# 17-ECP5_FPGA_2.net
KiCad netlist of a schematic drawn in Altium Designer
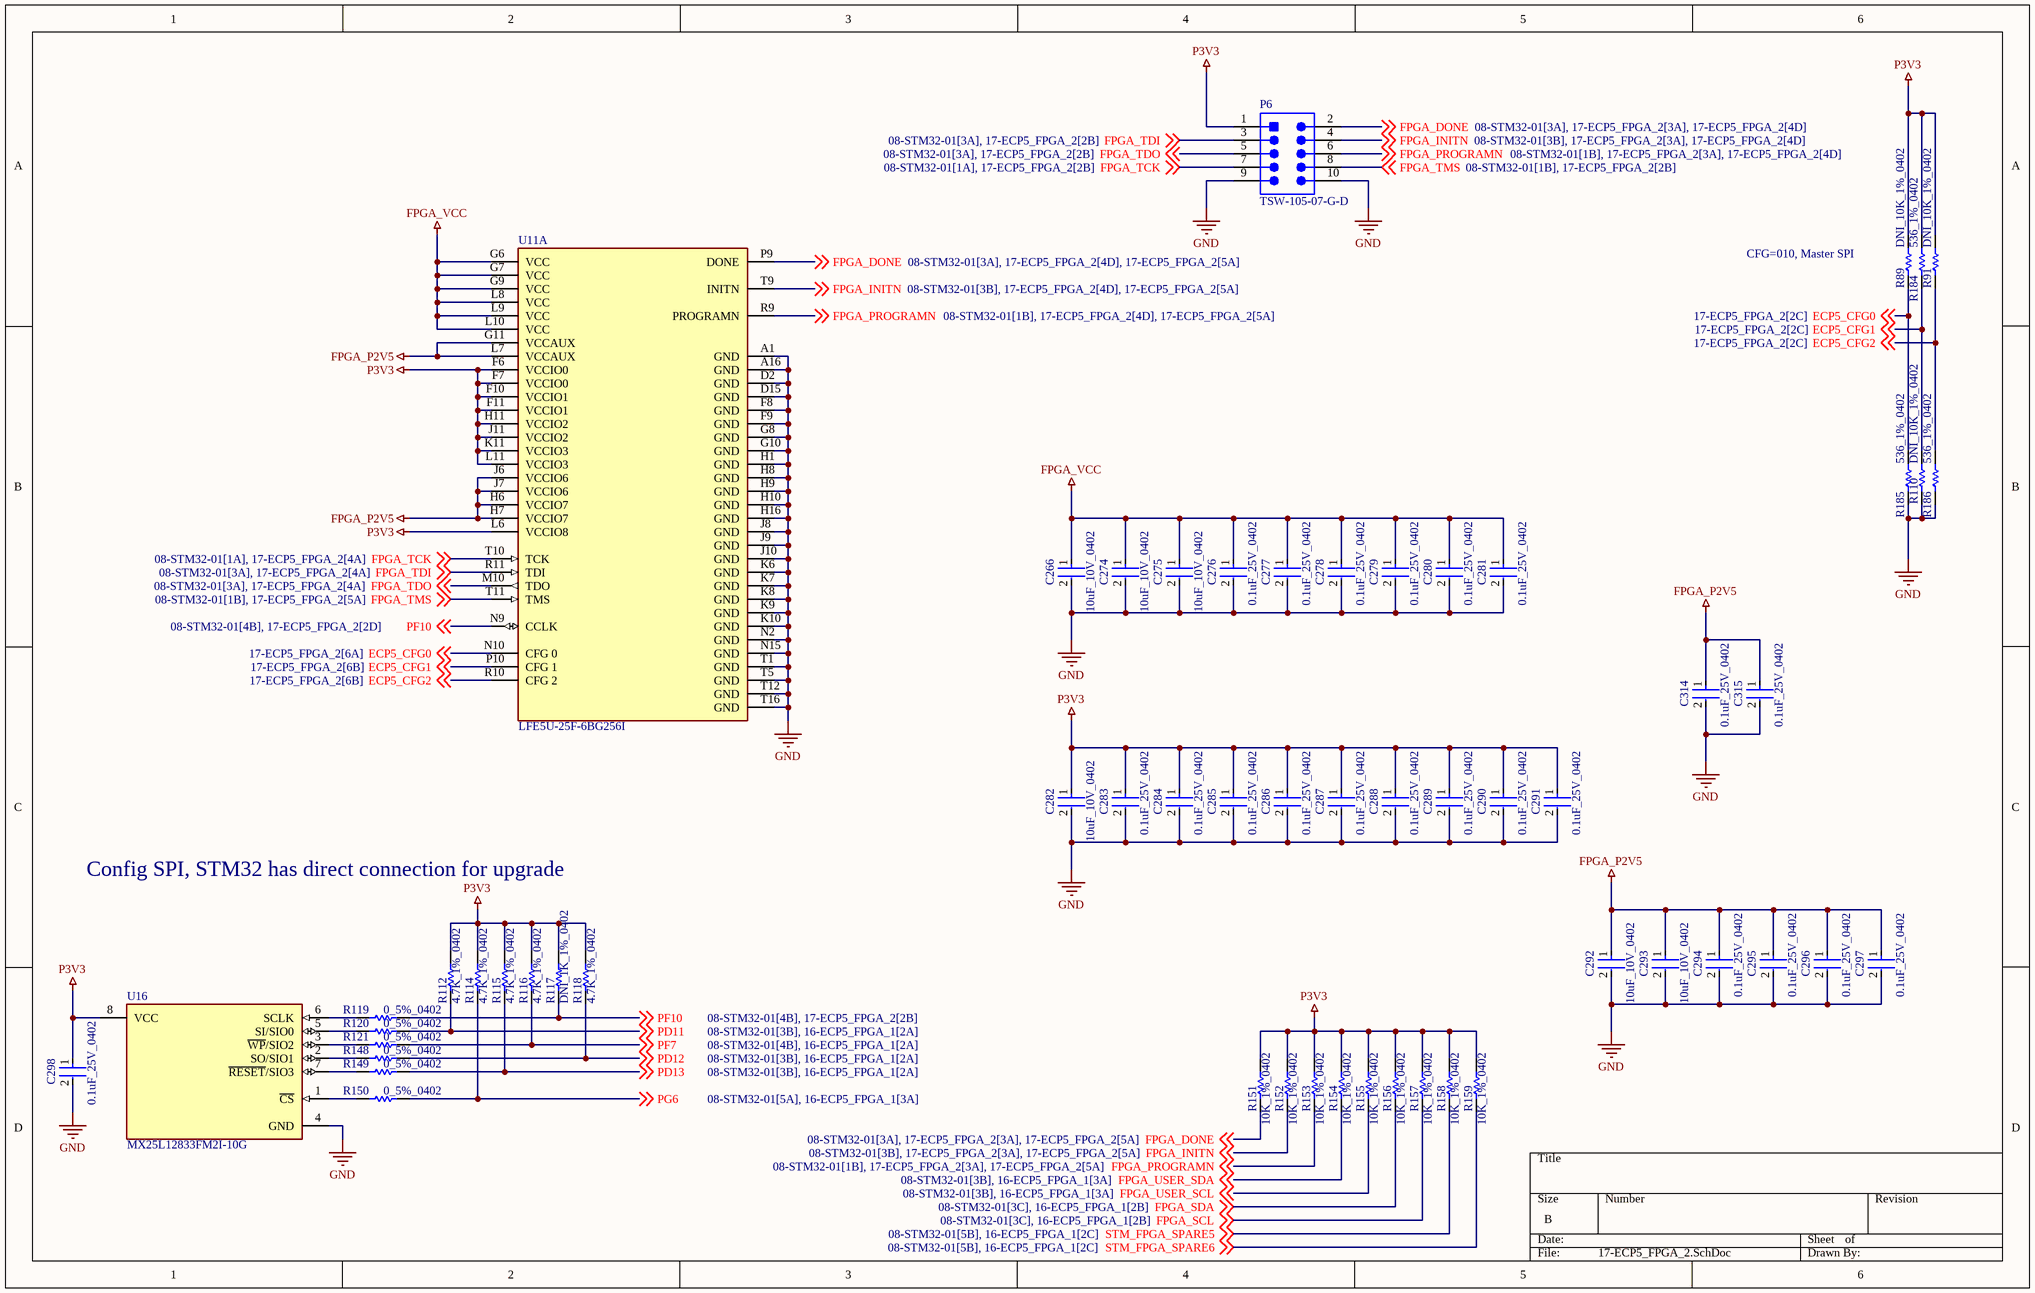
[diagram p0: 17-ECP5_FPGA_2.SchDoc]

(export (version "E")
  (design (tool "Eeschema 10.0.6"))
  (components
    (comp (ref "C266")
      (value "10uF_10V_0402")
      (footprint "FP-CL05A106MP5NUNC-MFG")
      (description "CAP CER 10UF 10V X5R 0402")
      (fields
        (field (name "OCTOPART") "https://octopart.com/cl05a106mp5nunc-samsung-22457395")
        (field (name "TOLERANCE") "20%")
      )
      (libsource (lib "Altium Content Vault") (part "b4654b650e69147ec39a6b967a45e02"))
    )
    (comp (ref "C274")
      (value "10uF_10V_0402")
      (footprint "FP-CL05A106MP5NUNC-MFG")
      (description "CAP CER 10UF 10V X5R 0402")
      (fields
        (field (name "OCTOPART") "https://octopart.com/cl05a106mp5nunc-samsung-22457395")
        (field (name "TOLERANCE") "20%")
      )
      (libsource (lib "Altium Content Vault") (part "b4654b650e69147ec39a6b967a45e02"))
    )
    (comp (ref "C275")
      (value "10uF_10V_0402")
      (footprint "FP-CL05A106MP5NUNC-MFG")
      (description "CAP CER 10UF 10V X5R 0402")
      (fields
        (field (name "OCTOPART") "https://octopart.com/cl05a106mp5nunc-samsung-22457395")
        (field (name "TOLERANCE") "20%")
      )
      (libsource (lib "Altium Content Vault") (part "b4654b650e69147ec39a6b967a45e02"))
    )
    (comp (ref "C276")
      (value "0.1uF_25V_0402")
      (footprint "FP-0402-L_1_0_1-W_0_5_0_1-IPC_C")
      (description "General Purpose Ceramic Capacitor, 0402, 100nF, 10%, X7R, 15%, 25V")
      (fields (field (name "VOLTAGE") "25V") (field (name "TOLERANCE") "10%"))
      (libsource (lib "Altium Content Vault") (part "b4654b650e69147ec39a6b967a45e02"))
    )
    (comp (ref "C277")
      (value "0.1uF_25V_0402")
      (footprint "FP-0402-L_1_0_1-W_0_5_0_1-IPC_C")
      (description "General Purpose Ceramic Capacitor, 0402, 100nF, 10%, X7R, 15%, 25V")
      (fields (field (name "VOLTAGE") "25V") (field (name "TOLERANCE") "10%"))
      (libsource (lib "Altium Content Vault") (part "b4654b650e69147ec39a6b967a45e02"))
    )
    (comp (ref "C278")
      (value "0.1uF_25V_0402")
      (footprint "FP-0402-L_1_0_1-W_0_5_0_1-IPC_C")
      (description "General Purpose Ceramic Capacitor, 0402, 100nF, 10%, X7R, 15%, 25V")
      (fields (field (name "VOLTAGE") "25V") (field (name "TOLERANCE") "10%"))
      (libsource (lib "Altium Content Vault") (part "b4654b650e69147ec39a6b967a45e02"))
    )
    (comp (ref "C279")
      (value "0.1uF_25V_0402")
      (footprint "FP-0402-L_1_0_1-W_0_5_0_1-IPC_C")
      (description "General Purpose Ceramic Capacitor, 0402, 100nF, 10%, X7R, 15%, 25V")
      (fields (field (name "VOLTAGE") "25V") (field (name "TOLERANCE") "10%"))
      (libsource (lib "Altium Content Vault") (part "b4654b650e69147ec39a6b967a45e02"))
    )
    (comp (ref "C280")
      (value "0.1uF_25V_0402")
      (footprint "FP-0402-L_1_0_1-W_0_5_0_1-IPC_C")
      (description "General Purpose Ceramic Capacitor, 0402, 100nF, 10%, X7R, 15%, 25V")
      (fields (field (name "VOLTAGE") "25V") (field (name "TOLERANCE") "10%"))
      (libsource (lib "Altium Content Vault") (part "b4654b650e69147ec39a6b967a45e02"))
    )
    (comp (ref "C281")
      (value "0.1uF_25V_0402")
      (footprint "FP-0402-L_1_0_1-W_0_5_0_1-IPC_C")
      (description "General Purpose Ceramic Capacitor, 0402, 100nF, 10%, X7R, 15%, 25V")
      (fields (field (name "VOLTAGE") "25V") (field (name "TOLERANCE") "10%"))
      (libsource (lib "Altium Content Vault") (part "b4654b650e69147ec39a6b967a45e02"))
    )
    (comp (ref "C282")
      (value "10uF_10V_0402")
      (footprint "FP-CL05A106MP5NUNC-MFG")
      (description "CAP CER 10UF 10V X5R 0402")
      (fields
        (field (name "OCTOPART") "https://octopart.com/cl05a106mp5nunc-samsung-22457395")
        (field (name "TOLERANCE") "20%")
      )
      (libsource (lib "Altium Content Vault") (part "b4654b650e69147ec39a6b967a45e02"))
    )
    (comp (ref "C283")
      (value "0.1uF_25V_0402")
      (footprint "FP-0402-L_1_0_1-W_0_5_0_1-IPC_C")
      (description "General Purpose Ceramic Capacitor, 0402, 100nF, 10%, X7R, 15%, 25V")
      (fields (field (name "VOLTAGE") "25V") (field (name "TOLERANCE") "10%"))
      (libsource (lib "Altium Content Vault") (part "b4654b650e69147ec39a6b967a45e02"))
    )
    (comp (ref "C284")
      (value "0.1uF_25V_0402")
      (footprint "FP-0402-L_1_0_1-W_0_5_0_1-IPC_C")
      (description "General Purpose Ceramic Capacitor, 0402, 100nF, 10%, X7R, 15%, 25V")
      (fields (field (name "VOLTAGE") "25V") (field (name "TOLERANCE") "10%"))
      (libsource (lib "Altium Content Vault") (part "b4654b650e69147ec39a6b967a45e02"))
    )
    (comp (ref "C285")
      (value "0.1uF_25V_0402")
      (footprint "FP-0402-L_1_0_1-W_0_5_0_1-IPC_C")
      (description "General Purpose Ceramic Capacitor, 0402, 100nF, 10%, X7R, 15%, 25V")
      (fields (field (name "VOLTAGE") "25V") (field (name "TOLERANCE") "10%"))
      (libsource (lib "Altium Content Vault") (part "b4654b650e69147ec39a6b967a45e02"))
    )
    (comp (ref "C286")
      (value "0.1uF_25V_0402")
      (footprint "FP-0402-L_1_0_1-W_0_5_0_1-IPC_C")
      (description "General Purpose Ceramic Capacitor, 0402, 100nF, 10%, X7R, 15%, 25V")
      (fields (field (name "VOLTAGE") "25V") (field (name "TOLERANCE") "10%"))
      (libsource (lib "Altium Content Vault") (part "b4654b650e69147ec39a6b967a45e02"))
    )
    (comp (ref "C287")
      (value "0.1uF_25V_0402")
      (footprint "FP-0402-L_1_0_1-W_0_5_0_1-IPC_C")
      (description "General Purpose Ceramic Capacitor, 0402, 100nF, 10%, X7R, 15%, 25V")
      (fields (field (name "VOLTAGE") "25V") (field (name "TOLERANCE") "10%"))
      (libsource (lib "Altium Content Vault") (part "b4654b650e69147ec39a6b967a45e02"))
    )
    (comp (ref "C288")
      (value "0.1uF_25V_0402")
      (footprint "FP-0402-L_1_0_1-W_0_5_0_1-IPC_C")
      (description "General Purpose Ceramic Capacitor, 0402, 100nF, 10%, X7R, 15%, 25V")
      (fields (field (name "VOLTAGE") "25V") (field (name "TOLERANCE") "10%"))
      (libsource (lib "Altium Content Vault") (part "b4654b650e69147ec39a6b967a45e02"))
    )
    (comp (ref "C289")
      (value "0.1uF_25V_0402")
      (footprint "FP-0402-L_1_0_1-W_0_5_0_1-IPC_C")
      (description "General Purpose Ceramic Capacitor, 0402, 100nF, 10%, X7R, 15%, 25V")
      (fields (field (name "VOLTAGE") "25V") (field (name "TOLERANCE") "10%"))
      (libsource (lib "Altium Content Vault") (part "b4654b650e69147ec39a6b967a45e02"))
    )
    (comp (ref "C290")
      (value "0.1uF_25V_0402")
      (footprint "FP-0402-L_1_0_1-W_0_5_0_1-IPC_C")
      (description "General Purpose Ceramic Capacitor, 0402, 100nF, 10%, X7R, 15%, 25V")
      (fields (field (name "VOLTAGE") "25V") (field (name "TOLERANCE") "10%"))
      (libsource (lib "Altium Content Vault") (part "b4654b650e69147ec39a6b967a45e02"))
    )
    (comp (ref "C291")
      (value "0.1uF_25V_0402")
      (footprint "FP-0402-L_1_0_1-W_0_5_0_1-IPC_C")
      (description "General Purpose Ceramic Capacitor, 0402, 100nF, 10%, X7R, 15%, 25V")
      (fields (field (name "VOLTAGE") "25V") (field (name "TOLERANCE") "10%"))
      (libsource (lib "Altium Content Vault") (part "b4654b650e69147ec39a6b967a45e02"))
    )
    (comp (ref "C292")
      (value "10uF_10V_0402")
      (footprint "FP-CL05A106MP5NUNC-MFG")
      (description "CAP CER 10UF 10V X5R 0402")
      (fields
        (field (name "OCTOPART") "https://octopart.com/cl05a106mp5nunc-samsung-22457395")
        (field (name "TOLERANCE") "20%")
      )
      (libsource (lib "Altium Content Vault") (part "b4654b650e69147ec39a6b967a45e02"))
    )
    (comp (ref "C293")
      (value "10uF_10V_0402")
      (footprint "FP-CL05A106MP5NUNC-MFG")
      (description "CAP CER 10UF 10V X5R 0402")
      (fields
        (field (name "OCTOPART") "https://octopart.com/cl05a106mp5nunc-samsung-22457395")
        (field (name "TOLERANCE") "20%")
      )
      (libsource (lib "Altium Content Vault") (part "b4654b650e69147ec39a6b967a45e02"))
    )
    (comp (ref "C294")
      (value "0.1uF_25V_0402")
      (footprint "FP-0402-L_1_0_1-W_0_5_0_1-IPC_C")
      (description "General Purpose Ceramic Capacitor, 0402, 100nF, 10%, X7R, 15%, 25V")
      (fields (field (name "VOLTAGE") "25V") (field (name "TOLERANCE") "10%"))
      (libsource (lib "Altium Content Vault") (part "b4654b650e69147ec39a6b967a45e02"))
    )
    (comp (ref "C295")
      (value "0.1uF_25V_0402")
      (footprint "FP-0402-L_1_0_1-W_0_5_0_1-IPC_C")
      (description "General Purpose Ceramic Capacitor, 0402, 100nF, 10%, X7R, 15%, 25V")
      (fields (field (name "VOLTAGE") "25V") (field (name "TOLERANCE") "10%"))
      (libsource (lib "Altium Content Vault") (part "b4654b650e69147ec39a6b967a45e02"))
    )
    (comp (ref "C296")
      (value "0.1uF_25V_0402")
      (footprint "FP-0402-L_1_0_1-W_0_5_0_1-IPC_C")
      (description "General Purpose Ceramic Capacitor, 0402, 100nF, 10%, X7R, 15%, 25V")
      (fields (field (name "VOLTAGE") "25V") (field (name "TOLERANCE") "10%"))
      (libsource (lib "Altium Content Vault") (part "b4654b650e69147ec39a6b967a45e02"))
    )
    (comp (ref "C297")
      (value "0.1uF_25V_0402")
      (footprint "FP-0402-L_1_0_1-W_0_5_0_1-IPC_C")
      (description "General Purpose Ceramic Capacitor, 0402, 100nF, 10%, X7R, 15%, 25V")
      (fields (field (name "VOLTAGE") "25V") (field (name "TOLERANCE") "10%"))
      (libsource (lib "Altium Content Vault") (part "b4654b650e69147ec39a6b967a45e02"))
    )
    (comp (ref "C298")
      (value "0.1uF_25V_0402")
      (footprint "FP-0402-L_1_0_1-W_0_5_0_1-IPC_C")
      (description "General Purpose Ceramic Capacitor, 0402, 100nF, 10%, X7R, 15%, 25V")
      (fields (field (name "VOLTAGE") "25V") (field (name "TOLERANCE") "10%"))
      (libsource (lib "Altium Content Vault") (part "b4654b650e69147ec39a6b967a45e02"))
    )
    (comp (ref "C314")
      (value "0.1uF_25V_0402")
      (footprint "FP-0402-L_1_0_1-W_0_5_0_1-IPC_C")
      (description "General Purpose Ceramic Capacitor, 0402, 100nF, 10%, X7R, 15%, 25V")
      (fields (field (name "VOLTAGE") "25V") (field (name "TOLERANCE") "10%"))
      (libsource (lib "Altium Content Vault") (part "b4654b650e69147ec39a6b967a45e02"))
    )
    (comp (ref "C315")
      (value "0.1uF_25V_0402")
      (footprint "FP-0402-L_1_0_1-W_0_5_0_1-IPC_C")
      (description "General Purpose Ceramic Capacitor, 0402, 100nF, 10%, X7R, 15%, 25V")
      (fields (field (name "VOLTAGE") "25V") (field (name "TOLERANCE") "10%"))
      (libsource (lib "Altium Content Vault") (part "b4654b650e69147ec39a6b967a45e02"))
    )
    (comp (ref "P6")
      (value "TSW-105-07-G-D")
      (footprint "SMTC-TSW-105-07-G-D_V")
      (fields (field (name "MANUFACTURER") "Samtec-Inc."))
      (libsource (lib "Altium Content Vault") (part "CN-2P-M-R10"))
    )
    (comp (ref "R89")
      (value "DNI_10K_1%_0402")
      (footprint "RESC1005X40X25NL10T10")
      (fields (field (name "MANUFACTURER") "Bourns") (field (name "PART NUMBER") "CR0402-FX-1002GLF"))
      (libsource (lib "Altium Content Vault") (part "RES"))
    )
    (comp (ref "R91")
      (value "DNI_10K_1%_0402")
      (footprint "RESC1005X40X25NL10T10")
      (fields (field (name "MANUFACTURER") "Bourns") (field (name "PART NUMBER") "CR0402-FX-1002GLF"))
      (libsource (lib "Altium Content Vault") (part "RES"))
    )
    (comp (ref "R110")
      (value "DNI_10K_1%_0402")
      (footprint "RESC1005X40X25NL10T10")
      (fields (field (name "MANUFACTURER") "Bourns") (field (name "PART NUMBER") "CR0402-FX-1002GLF"))
      (libsource (lib "Altium Content Vault") (part "RES"))
    )
    (comp (ref "R112")
      (value "4.7K_1%_0402")
      (footprint "RESC1005X40X25NL10T10")
      (fields (field (name "MANUFACTURER") "Bourns") (field (name "PART NUMBER") "CR0402-FX-4701GLF"))
      (libsource (lib "Altium Content Vault") (part "RES"))
    )
    (comp (ref "R114")
      (value "4.7K_1%_0402")
      (footprint "RESC1005X40X25NL10T10")
      (fields (field (name "MANUFACTURER") "Bourns") (field (name "PART NUMBER") "CR0402-FX-4701GLF"))
      (libsource (lib "Altium Content Vault") (part "RES"))
    )
    (comp (ref "R115")
      (value "4.7K_1%_0402")
      (footprint "RESC1005X40X25NL10T10")
      (fields (field (name "MANUFACTURER") "Bourns") (field (name "PART NUMBER") "CR0402-FX-4701GLF"))
      (libsource (lib "Altium Content Vault") (part "RES"))
    )
    (comp (ref "R116")
      (value "4.7K_1%_0402")
      (footprint "RESC1005X40X25NL10T10")
      (fields (field (name "MANUFACTURER") "Bourns") (field (name "PART NUMBER") "CR0402-FX-4701GLF"))
      (libsource (lib "Altium Content Vault") (part "RES"))
    )
    (comp (ref "R117")
      (value "DNI_1K_1%_0402")
      (footprint "RESC1005X40X25LL05T10")
      (fields (field (name "PART NUMBER") "CRCW04021K00FKEDHP") (field (name "MANUFACTURER") "Vishay Dale"))
      (libsource (lib "Altium Content Vault") (part "RES"))
    )
    (comp (ref "R118")
      (value "4.7K_1%_0402")
      (footprint "RESC1005X40X25NL10T10")
      (fields (field (name "MANUFACTURER") "Bourns") (field (name "PART NUMBER") "CR0402-FX-4701GLF"))
      (libsource (lib "Altium Content Vault") (part "RES"))
    )
    (comp (ref "R119")
      (value "0_5%_0402")
      (footprint "RESC1005X40X25NL05T10")
      (fields (field (name "MANUFACTURER") "Panasonic") (field (name "PART NUMBER") "ERJ-U020R00X"))
      (libsource (lib "Altium Content Vault") (part "RES"))
    )
    (comp (ref "R120")
      (value "0_5%_0402")
      (footprint "RESC1005X40X25NL05T10")
      (fields (field (name "MANUFACTURER") "Panasonic") (field (name "PART NUMBER") "ERJ-U020R00X"))
      (libsource (lib "Altium Content Vault") (part "RES"))
    )
    (comp (ref "R121")
      (value "0_5%_0402")
      (footprint "RESC1005X40X25NL05T10")
      (fields (field (name "MANUFACTURER") "Panasonic") (field (name "PART NUMBER") "ERJ-U020R00X"))
      (libsource (lib "Altium Content Vault") (part "RES"))
    )
    (comp (ref "R148")
      (value "0_5%_0402")
      (footprint "RESC1005X40X25NL05T10")
      (fields (field (name "MANUFACTURER") "Panasonic") (field (name "PART NUMBER") "ERJ-U020R00X"))
      (libsource (lib "Altium Content Vault") (part "RES"))
    )
    (comp (ref "R149")
      (value "0_5%_0402")
      (footprint "RESC1005X40X25NL05T10")
      (fields (field (name "MANUFACTURER") "Panasonic") (field (name "PART NUMBER") "ERJ-U020R00X"))
      (libsource (lib "Altium Content Vault") (part "RES"))
    )
    (comp (ref "R150")
      (value "0_5%_0402")
      (footprint "RESC1005X40X25NL05T10")
      (fields (field (name "MANUFACTURER") "Panasonic") (field (name "PART NUMBER") "ERJ-U020R00X"))
      (libsource (lib "Altium Content Vault") (part "RES"))
    )
    (comp (ref "R151")
      (value "10K_1%_0402")
      (footprint "RESC1005X40X25NL10T10")
      (fields (field (name "MANUFACTURER") "Bourns") (field (name "PART NUMBER") "CR0402-FX-1002GLF"))
      (libsource (lib "Altium Content Vault") (part "RES"))
    )
    (comp (ref "R152")
      (value "10K_1%_0402")
      (footprint "RESC1005X40X25NL10T10")
      (fields (field (name "MANUFACTURER") "Bourns") (field (name "PART NUMBER") "CR0402-FX-1002GLF"))
      (libsource (lib "Altium Content Vault") (part "RES"))
    )
    (comp (ref "R153")
      (value "10K_1%_0402")
      (footprint "RESC1005X40X25NL10T10")
      (fields (field (name "MANUFACTURER") "Bourns") (field (name "PART NUMBER") "CR0402-FX-1002GLF"))
      (libsource (lib "Altium Content Vault") (part "RES"))
    )
    (comp (ref "R154")
      (value "10K_1%_0402")
      (footprint "RESC1005X40X25NL10T10")
      (fields (field (name "MANUFACTURER") "Bourns") (field (name "PART NUMBER") "CR0402-FX-1002GLF"))
      (libsource (lib "Altium Content Vault") (part "RES"))
    )
    (comp (ref "R155")
      (value "10K_1%_0402")
      (footprint "RESC1005X40X25NL10T10")
      (fields (field (name "MANUFACTURER") "Bourns") (field (name "PART NUMBER") "CR0402-FX-1002GLF"))
      (libsource (lib "Altium Content Vault") (part "RES"))
    )
    (comp (ref "R156")
      (value "10K_1%_0402")
      (footprint "RESC1005X40X25NL10T10")
      (fields (field (name "MANUFACTURER") "Bourns") (field (name "PART NUMBER") "CR0402-FX-1002GLF"))
      (libsource (lib "Altium Content Vault") (part "RES"))
    )
    (comp (ref "R157")
      (value "10K_1%_0402")
      (footprint "RESC1005X40X25NL10T10")
      (fields (field (name "MANUFACTURER") "Bourns") (field (name "PART NUMBER") "CR0402-FX-1002GLF"))
      (libsource (lib "Altium Content Vault") (part "RES"))
    )
    (comp (ref "R158")
      (value "10K_1%_0402")
      (footprint "RESC1005X40X25NL10T10")
      (fields (field (name "MANUFACTURER") "Bourns") (field (name "PART NUMBER") "CR0402-FX-1002GLF"))
      (libsource (lib "Altium Content Vault") (part "RES"))
    )
    (comp (ref "R159")
      (value "10K_1%_0402")
      (footprint "RESC1005X40X25NL10T10")
      (fields (field (name "MANUFACTURER") "Bourns") (field (name "PART NUMBER") "CR0402-FX-1002GLF"))
      (libsource (lib "Altium Content Vault") (part "RES"))
    )
    (comp (ref "R184")
      (value "536_1%_0402")
      (footprint "RESC1005X40X25NL05T05")
      (fields (field (name "MANUFACTURER") "Panasonic") (field (name "PART NUMBER") "ERJ-2RKF5360X"))
      (libsource (lib "Altium Content Vault") (part "RES"))
    )
    (comp (ref "R185")
      (value "536_1%_0402")
      (footprint "RESC1005X40X25NL05T05")
      (fields (field (name "MANUFACTURER") "Panasonic") (field (name "PART NUMBER") "ERJ-2RKF5360X"))
      (libsource (lib "Altium Content Vault") (part "RES"))
    )
    (comp (ref "R186")
      (value "536_1%_0402")
      (footprint "RESC1005X40X25NL05T05")
      (fields (field (name "MANUFACTURER") "Panasonic") (field (name "PART NUMBER") "ERJ-2RKF5360X"))
      (libsource (lib "Altium Content Vault") (part "RES"))
    )
    (comp (ref "U11")
      (value "LFE5U-25F-6BG256I")
      (footprint "FP-LFE5U-25F-6BG256I-MFG")
      (description "IC FPGA 197 I/O 256CABGA")
      (libsource (lib "Altium Content Vault") (part "bfd34961a1b5a598594aee4faf9689d"))
    )
    (comp (ref "U16")
      (value "MX25L12833FM2I-10G")
      (footprint "FP-MX25L12833FM2I-10G-MFG")
      (description "IC FLASH 128MBIT SPI/QUAD 8SOP")
      (libsource (lib "Altium Content Vault") (part "3d93ad905be0c27c551c1345014b9ea"))
    )
  )
  (nets
    (net (code "1") (name "ECP5_CFG0") (class "Default")
      (node (ref "R185") (pin "2") (pinfunction "2_2") (pintype "passive"))
      (node (ref "R89") (pin "1") (pinfunction "1_1") (pintype "passive"))
      (node (ref "U11") (pin "N10") (pinfunction "CFG_0_N10") (pintype "passive"))
    )
    (net (code "2") (name "ECP5_CFG1") (class "Default")
      (node (ref "R110") (pin "2") (pinfunction "2_2") (pintype "passive"))
      (node (ref "R184") (pin "1") (pinfunction "1_1") (pintype "passive"))
      (node (ref "U11") (pin "P10") (pinfunction "CFG_1_P10") (pintype "passive"))
    )
    (net (code "3") (name "ECP5_CFG2") (class "Default")
      (node (ref "R186") (pin "2") (pinfunction "2_2") (pintype "passive"))
      (node (ref "R91") (pin "1") (pinfunction "1_1") (pintype "passive"))
      (node (ref "U11") (pin "R10") (pinfunction "CFG_2_R10") (pintype "passive"))
    )
    (net (code "4") (name "FPGA_DONE") (class "Default")
      (node (ref "P6") (pin "2") (pinfunction "2_2") (pintype "passive"))
      (node (ref "R151") (pin "1") (pinfunction "1_1") (pintype "passive"))
      (node (ref "U11") (pin "P9") (pinfunction "DONE_P9") (pintype "passive"))
    )
    (net (code "5") (name "FPGA_INITN") (class "Default")
      (node (ref "P6") (pin "4") (pinfunction "4_4") (pintype "passive"))
      (node (ref "R152") (pin "1") (pinfunction "1_1") (pintype "passive"))
      (node (ref "U11") (pin "T9") (pinfunction "INITN_T9") (pintype "passive"))
    )
    (net (code "6") (name "FPGA_P2V5") (class "Default")
      (node (ref "C292") (pin "1") (pinfunction "1_1") (pintype "passive"))
      (node (ref "C293") (pin "1") (pinfunction "1_1") (pintype "passive"))
      (node (ref "C294") (pin "1") (pinfunction "1_1") (pintype "passive"))
      (node (ref "C295") (pin "1") (pinfunction "1_1") (pintype "passive"))
      (node (ref "C296") (pin "1") (pinfunction "1_1") (pintype "passive"))
      (node (ref "C297") (pin "1") (pinfunction "1_1") (pintype "passive"))
      (node (ref "C314") (pin "1") (pinfunction "1_1") (pintype "passive"))
      (node (ref "C315") (pin "1") (pinfunction "1_1") (pintype "passive"))
      (node (ref "U11") (pin "G11") (pinfunction "VCCAUX_G11") (pintype "power_in"))
      (node (ref "U11") (pin "H6") (pinfunction "VCCIO7_H6") (pintype "power_in"))
      (node (ref "U11") (pin "H7") (pinfunction "VCCIO7_H7") (pintype "power_in"))
      (node (ref "U11") (pin "J6") (pinfunction "VCCIO6_J6") (pintype "power_in"))
      (node (ref "U11") (pin "J7") (pinfunction "VCCIO6_J7") (pintype "power_in"))
      (node (ref "U11") (pin "L7") (pinfunction "VCCAUX_L7") (pintype "power_in"))
    )
    (net (code "7") (name "FPGA_PROGRAMN") (class "Default")
      (node (ref "P6") (pin "6") (pinfunction "6_6") (pintype "passive"))
      (node (ref "R153") (pin "1") (pinfunction "1_1") (pintype "passive"))
      (node (ref "U11") (pin "R9") (pinfunction "PROGRAMN_R9") (pintype "passive"))
    )
    (net (code "8") (name "FPGA_SCL") (class "Default")
      (node (ref "R157") (pin "1") (pinfunction "1_1") (pintype "passive"))
    )
    (net (code "9") (name "FPGA_SDA") (class "Default")
      (node (ref "R156") (pin "1") (pinfunction "1_1") (pintype "passive"))
    )
    (net (code "10") (name "FPGA_TCK") (class "Default")
      (node (ref "P6") (pin "7") (pinfunction "7_7") (pintype "passive"))
      (node (ref "U11") (pin "T10") (pinfunction "TCK_T10") (pintype "input"))
    )
    (net (code "11") (name "FPGA_TDI") (class "Default")
      (node (ref "P6") (pin "3") (pinfunction "3_3") (pintype "passive"))
      (node (ref "U11") (pin "R11") (pinfunction "TDI_R11") (pintype "input"))
    )
    (net (code "12") (name "FPGA_TDO") (class "Default")
      (node (ref "P6") (pin "5") (pinfunction "5_5") (pintype "passive"))
      (node (ref "U11") (pin "M10") (pinfunction "TDO_M10") (pintype "output"))
    )
    (net (code "13") (name "FPGA_TMS") (class "Default")
      (node (ref "P6") (pin "8") (pinfunction "8_8") (pintype "passive"))
      (node (ref "U11") (pin "T11") (pinfunction "TMS_T11") (pintype "input"))
    )
    (net (code "14") (name "FPGA_USER_SCL") (class "Default")
      (node (ref "R155") (pin "1") (pinfunction "1_1") (pintype "passive"))
    )
    (net (code "15") (name "FPGA_USER_SDA") (class "Default")
      (node (ref "R154") (pin "1") (pinfunction "1_1") (pintype "passive"))
    )
    (net (code "16") (name "FPGA_VCC") (class "Default")
      (node (ref "C266") (pin "1") (pinfunction "1_1") (pintype "passive"))
      (node (ref "C274") (pin "1") (pinfunction "1_1") (pintype "passive"))
      (node (ref "C275") (pin "1") (pinfunction "1_1") (pintype "passive"))
      (node (ref "C276") (pin "1") (pinfunction "1_1") (pintype "passive"))
      (node (ref "C277") (pin "1") (pinfunction "1_1") (pintype "passive"))
      (node (ref "C278") (pin "1") (pinfunction "1_1") (pintype "passive"))
      (node (ref "C279") (pin "1") (pinfunction "1_1") (pintype "passive"))
      (node (ref "C280") (pin "1") (pinfunction "1_1") (pintype "passive"))
      (node (ref "C281") (pin "1") (pinfunction "1_1") (pintype "passive"))
      (node (ref "U11") (pin "G6") (pinfunction "VCC_G6") (pintype "power_in"))
      (node (ref "U11") (pin "G7") (pinfunction "VCC_G7") (pintype "power_in"))
      (node (ref "U11") (pin "G9") (pinfunction "VCC_G9") (pintype "power_in"))
      (node (ref "U11") (pin "L10") (pinfunction "VCC_L10") (pintype "power_in"))
      (node (ref "U11") (pin "L8") (pinfunction "VCC_L8") (pintype "power_in"))
      (node (ref "U11") (pin "L9") (pinfunction "VCC_L9") (pintype "power_in"))
    )
    (net (code "17") (name "GND") (class "Default")
      (node (ref "C266") (pin "2") (pinfunction "2_2") (pintype "passive"))
      (node (ref "C274") (pin "2") (pinfunction "2_2") (pintype "passive"))
      (node (ref "C275") (pin "2") (pinfunction "2_2") (pintype "passive"))
      (node (ref "C276") (pin "2") (pinfunction "2_2") (pintype "passive"))
      (node (ref "C277") (pin "2") (pinfunction "2_2") (pintype "passive"))
      (node (ref "C278") (pin "2") (pinfunction "2_2") (pintype "passive"))
      (node (ref "C279") (pin "2") (pinfunction "2_2") (pintype "passive"))
      (node (ref "C280") (pin "2") (pinfunction "2_2") (pintype "passive"))
      (node (ref "C281") (pin "2") (pinfunction "2_2") (pintype "passive"))
      (node (ref "C282") (pin "2") (pinfunction "2_2") (pintype "passive"))
      (node (ref "C283") (pin "2") (pinfunction "2_2") (pintype "passive"))
      (node (ref "C284") (pin "2") (pinfunction "2_2") (pintype "passive"))
      (node (ref "C285") (pin "2") (pinfunction "2_2") (pintype "passive"))
      (node (ref "C286") (pin "2") (pinfunction "2_2") (pintype "passive"))
      (node (ref "C287") (pin "2") (pinfunction "2_2") (pintype "passive"))
      (node (ref "C288") (pin "2") (pinfunction "2_2") (pintype "passive"))
      (node (ref "C289") (pin "2") (pinfunction "2_2") (pintype "passive"))
      (node (ref "C290") (pin "2") (pinfunction "2_2") (pintype "passive"))
      (node (ref "C291") (pin "2") (pinfunction "2_2") (pintype "passive"))
      (node (ref "C292") (pin "2") (pinfunction "2_2") (pintype "passive"))
      (node (ref "C293") (pin "2") (pinfunction "2_2") (pintype "passive"))
      (node (ref "C294") (pin "2") (pinfunction "2_2") (pintype "passive"))
      (node (ref "C295") (pin "2") (pinfunction "2_2") (pintype "passive"))
      (node (ref "C296") (pin "2") (pinfunction "2_2") (pintype "passive"))
      (node (ref "C297") (pin "2") (pinfunction "2_2") (pintype "passive"))
      (node (ref "C298") (pin "2") (pinfunction "2_2") (pintype "passive"))
      (node (ref "C314") (pin "2") (pinfunction "2_2") (pintype "passive"))
      (node (ref "C315") (pin "2") (pinfunction "2_2") (pintype "passive"))
      (node (ref "P6") (pin "10") (pinfunction "10_10") (pintype "passive"))
      (node (ref "P6") (pin "9") (pinfunction "9_9") (pintype "passive"))
      (node (ref "R110") (pin "1") (pinfunction "1_1") (pintype "passive"))
      (node (ref "R185") (pin "1") (pinfunction "1_1") (pintype "passive"))
      (node (ref "R186") (pin "1") (pinfunction "1_1") (pintype "passive"))
      (node (ref "U11") (pin "A1") (pinfunction "GND_A1") (pintype "power_in"))
      (node (ref "U11") (pin "A16") (pinfunction "GND_A16") (pintype "power_in"))
      (node (ref "U11") (pin "D15") (pinfunction "GND_D15") (pintype "power_in"))
      (node (ref "U11") (pin "D2") (pinfunction "GND_D2") (pintype "power_in"))
      (node (ref "U11") (pin "F8") (pinfunction "GND_F8") (pintype "power_in"))
      (node (ref "U11") (pin "F9") (pinfunction "GND_F9") (pintype "power_in"))
      (node (ref "U11") (pin "G10") (pinfunction "GND_G10") (pintype "power_in"))
      (node (ref "U11") (pin "G8") (pinfunction "GND_G8") (pintype "power_in"))
      (node (ref "U11") (pin "H1") (pinfunction "GND_H1") (pintype "power_in"))
      (node (ref "U11") (pin "H10") (pinfunction "GND_H10") (pintype "power_in"))
      (node (ref "U11") (pin "H16") (pinfunction "GND_H16") (pintype "power_in"))
      (node (ref "U11") (pin "H8") (pinfunction "GND_H8") (pintype "power_in"))
      (node (ref "U11") (pin "H9") (pinfunction "GND_H9") (pintype "power_in"))
      (node (ref "U11") (pin "J10") (pinfunction "GND_J10") (pintype "power_in"))
      (node (ref "U11") (pin "J8") (pinfunction "GND_J8") (pintype "power_in"))
      (node (ref "U11") (pin "J9") (pinfunction "GND_J9") (pintype "power_in"))
      (node (ref "U11") (pin "K10") (pinfunction "GND_K10") (pintype "power_in"))
      (node (ref "U11") (pin "K6") (pinfunction "GND_K6") (pintype "power_in"))
      (node (ref "U11") (pin "K7") (pinfunction "GND_K7") (pintype "power_in"))
      (node (ref "U11") (pin "K8") (pinfunction "GND_K8") (pintype "power_in"))
      (node (ref "U11") (pin "K9") (pinfunction "GND_K9") (pintype "power_in"))
      (node (ref "U11") (pin "N15") (pinfunction "GND_N15") (pintype "power_in"))
      (node (ref "U11") (pin "N2") (pinfunction "GND_N2") (pintype "power_in"))
      (node (ref "U11") (pin "T1") (pinfunction "GND_T1") (pintype "power_in"))
      (node (ref "U11") (pin "T12") (pinfunction "GND_T12") (pintype "power_in"))
      (node (ref "U11") (pin "T16") (pinfunction "GND_T16") (pintype "power_in"))
      (node (ref "U11") (pin "T5") (pinfunction "GND_T5") (pintype "power_in"))
      (node (ref "U16") (pin "4") (pinfunction "GND_4") (pintype "power_in"))
    )
    (net (code "18") (name "Net-(U16-SCLK)") (class "Default")
      (node (ref "R119") (pin "1") (pinfunction "1_1") (pintype "passive"))
      (node (ref "U16") (pin "6") (pinfunction "SCLK_6") (pintype "input"))
    )
    (net (code "19") (name "Net-(U16-SI{slash}SIO0)") (class "Default")
      (node (ref "R120") (pin "1") (pinfunction "1_1") (pintype "passive"))
      (node (ref "U16") (pin "5") (pinfunction "SI/SIO0_5") (pintype "bidirectional"))
    )
    (net (code "20") (name "Net-(U16-SO{slash}SIO1)") (class "Default")
      (node (ref "R148") (pin "1") (pinfunction "1_1") (pintype "passive"))
      (node (ref "U16") (pin "2") (pinfunction "SO/SIO1_2") (pintype "bidirectional"))
    )
    (net (code "21") (name "Net-(U16-~{CS})") (class "Default")
      (node (ref "R150") (pin "1") (pinfunction "1_1") (pintype "passive"))
      (node (ref "U16") (pin "1") (pinfunction "~{CS}_1") (pintype "input"))
    )
    (net (code "22") (name "Net-(U16-~{RESET}{slash}SIO3)") (class "Default")
      (node (ref "R149") (pin "1") (pinfunction "1_1") (pintype "passive"))
      (node (ref "U16") (pin "7") (pinfunction "~{RESET}/SIO3_7") (pintype "bidirectional"))
    )
    (net (code "23") (name "Net-(U16-~{WP}{slash}SIO2)") (class "Default")
      (node (ref "R121") (pin "1") (pinfunction "1_1") (pintype "passive"))
      (node (ref "U16") (pin "3") (pinfunction "~{WP}/SIO2_3") (pintype "bidirectional"))
    )
    (net (code "24") (name "P3V3") (class "Default")
      (node (ref "C282") (pin "1") (pinfunction "1_1") (pintype "passive"))
      (node (ref "C283") (pin "1") (pinfunction "1_1") (pintype "passive"))
      (node (ref "C284") (pin "1") (pinfunction "1_1") (pintype "passive"))
      (node (ref "C285") (pin "1") (pinfunction "1_1") (pintype "passive"))
      (node (ref "C286") (pin "1") (pinfunction "1_1") (pintype "passive"))
      (node (ref "C287") (pin "1") (pinfunction "1_1") (pintype "passive"))
      (node (ref "C288") (pin "1") (pinfunction "1_1") (pintype "passive"))
      (node (ref "C289") (pin "1") (pinfunction "1_1") (pintype "passive"))
      (node (ref "C290") (pin "1") (pinfunction "1_1") (pintype "passive"))
      (node (ref "C291") (pin "1") (pinfunction "1_1") (pintype "passive"))
      (node (ref "C298") (pin "1") (pinfunction "1_1") (pintype "passive"))
      (node (ref "P6") (pin "1") (pinfunction "1_1") (pintype "passive"))
      (node (ref "R112") (pin "2") (pinfunction "2_2") (pintype "passive"))
      (node (ref "R114") (pin "2") (pinfunction "2_2") (pintype "passive"))
      (node (ref "R115") (pin "2") (pinfunction "2_2") (pintype "passive"))
      (node (ref "R116") (pin "2") (pinfunction "2_2") (pintype "passive"))
      (node (ref "R117") (pin "2") (pinfunction "2_2") (pintype "passive"))
      (node (ref "R118") (pin "2") (pinfunction "2_2") (pintype "passive"))
      (node (ref "R151") (pin "2") (pinfunction "2_2") (pintype "passive"))
      (node (ref "R152") (pin "2") (pinfunction "2_2") (pintype "passive"))
      (node (ref "R153") (pin "2") (pinfunction "2_2") (pintype "passive"))
      (node (ref "R154") (pin "2") (pinfunction "2_2") (pintype "passive"))
      (node (ref "R155") (pin "2") (pinfunction "2_2") (pintype "passive"))
      (node (ref "R156") (pin "2") (pinfunction "2_2") (pintype "passive"))
      (node (ref "R157") (pin "2") (pinfunction "2_2") (pintype "passive"))
      (node (ref "R158") (pin "2") (pinfunction "2_2") (pintype "passive"))
      (node (ref "R159") (pin "2") (pinfunction "2_2") (pintype "passive"))
      (node (ref "R184") (pin "2") (pinfunction "2_2") (pintype "passive"))
      (node (ref "R89") (pin "2") (pinfunction "2_2") (pintype "passive"))
      (node (ref "R91") (pin "2") (pinfunction "2_2") (pintype "passive"))
      (node (ref "U11") (pin "F10") (pinfunction "VCCIO1_F10") (pintype "power_in"))
      (node (ref "U11") (pin "F11") (pinfunction "VCCIO1_F11") (pintype "power_in"))
      (node (ref "U11") (pin "F6") (pinfunction "VCCIO0_F6") (pintype "power_in"))
      (node (ref "U11") (pin "F7") (pinfunction "VCCIO0_F7") (pintype "power_in"))
      (node (ref "U11") (pin "H11") (pinfunction "VCCIO2_H11") (pintype "power_in"))
      (node (ref "U11") (pin "J11") (pinfunction "VCCIO2_J11") (pintype "power_in"))
      (node (ref "U11") (pin "K11") (pinfunction "VCCIO3_K11") (pintype "power_in"))
      (node (ref "U11") (pin "L11") (pinfunction "VCCIO3_L11") (pintype "power_in"))
      (node (ref "U11") (pin "L6") (pinfunction "VCCIO8_L6") (pintype "power_in"))
      (node (ref "U16") (pin "8") (pinfunction "VCC_8") (pintype "power_in"))
    )
    (net (code "25") (name "PD11") (class "Default")
      (node (ref "R112") (pin "1") (pinfunction "1_1") (pintype "passive"))
      (node (ref "R120") (pin "2") (pinfunction "2_2") (pintype "passive"))
    )
    (net (code "26") (name "PD12") (class "Default")
      (node (ref "R118") (pin "1") (pinfunction "1_1") (pintype "passive"))
      (node (ref "R148") (pin "2") (pinfunction "2_2") (pintype "passive"))
    )
    (net (code "27") (name "PD13") (class "Default")
      (node (ref "R115") (pin "1") (pinfunction "1_1") (pintype "passive"))
      (node (ref "R149") (pin "2") (pinfunction "2_2") (pintype "passive"))
    )
    (net (code "28") (name "PF7") (class "Default")
      (node (ref "R116") (pin "1") (pinfunction "1_1") (pintype "passive"))
      (node (ref "R121") (pin "2") (pinfunction "2_2") (pintype "passive"))
    )
    (net (code "29") (name "PF10") (class "Default")
      (node (ref "R117") (pin "1") (pinfunction "1_1") (pintype "passive"))
      (node (ref "R119") (pin "2") (pinfunction "2_2") (pintype "passive"))
      (node (ref "U11") (pin "N9") (pinfunction "CCLK_N9") (pintype "bidirectional"))
    )
    (net (code "30") (name "PG6") (class "Default")
      (node (ref "R114") (pin "1") (pinfunction "1_1") (pintype "passive"))
      (node (ref "R150") (pin "2") (pinfunction "2_2") (pintype "passive"))
    )
    (net (code "31") (name "STM_FPGA_SPARE5") (class "Default")
      (node (ref "R158") (pin "1") (pinfunction "1_1") (pintype "passive"))
    )
    (net (code "32") (name "STM_FPGA_SPARE6") (class "Default")
      (node (ref "R159") (pin "1") (pinfunction "1_1") (pintype "passive"))
    )
  )
)
